# part5.net
KiCad netlist of a schematic drawn in Altium Designer
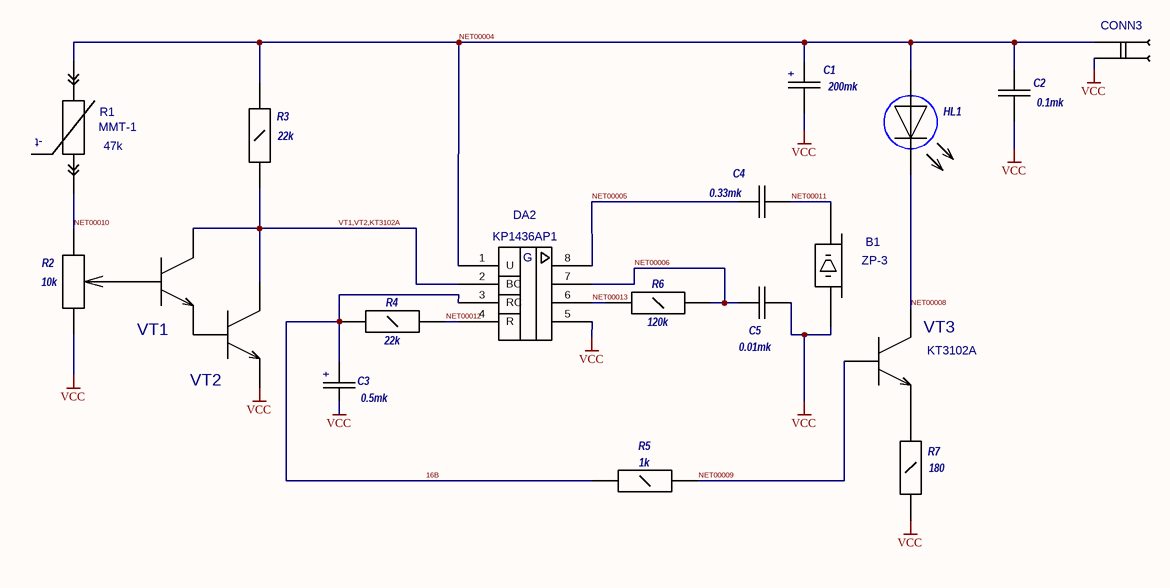
[diagram p0: part5.SCHDOC]

(export (version "E")
  (design (tool "Eeschema 10.0.6"))
  (components
    (comp (ref "B1") (value "ZP-3") (footprint "ЗП-3") (libsource (lib "*") (part "ZP-3")))
    (comp (ref "C1")
      (value "200mk")
      (footprint "К50-29 (17Х6)")
      (description "K50-29 (1;2,2;4,7;10;22 MK)")
      (libsource (lib "*") (part "K50-29 (1;2,2;4,7;10;22 MK)"))
    )
    (comp (ref "C2")
      (value "0.1mk")
      (footprint "K71-6 (10X4)")
      (description "K71-6 (5-30 МК)")
      (libsource (lib "*") (part "K71-6 (5-30 МК)"))
    )
    (comp (ref "C3")
      (value "0.5mk")
      (footprint "К50-29 (17Х6)")
      (description "K50-29 (1;2,2;4,7;10;22 MK)")
      (libsource (lib "*") (part "K50-29 (1;2,2;4,7;10;22 MK)"))
    )
    (comp (ref "C4")
      (value "0.33mk")
      (footprint "K71-6 (10X4)")
      (description "K71-6 (5-30 МК)")
      (libsource (lib "*") (part "K71-6 (5-30 МК)"))
    )
    (comp (ref "C5")
      (value "0.01mk")
      (footprint "K71-6 (10X4)")
      (description "K71-6 (5-30 МК)")
      (libsource (lib "*") (part "K71-6 (5-30 МК)"))
    )
    (comp (ref "CONN3") (value "CONN2X") (footprint "CONN2X") (libsource (lib "*") (part "CONN2X")))
    (comp (ref "DA2") (value "KP1436AP1") (footprint "КР1436АП1") (libsource (lib "*") (part "KP1436AP1")))
    (comp (ref "HL1") (value "АЛ307") (footprint "АЛ307") (libsource (lib "*") (part "АЛ307")))
    (comp (ref "R1")
      (value "MMT-1")
      (footprint "MMT-1")
      (fields (field (name "ALTIUM_VALUE") "47k"))
      (libsource (lib "*") (part "MMT-1"))
    )
    (comp (ref "R2")
      (value "10k")
      (footprint "СП3-38В")
      (description "СП3-38В")
      (libsource (lib "*") (part "СП3-38В"))
    )
    (comp (ref "R3")
      (value "22k")
      (footprint "МЛТ(0.25)")
      (description "МЛТ(0.25)")
      (libsource (lib "*") (part "МЛТ(0.25)"))
    )
    (comp (ref "R4")
      (value "22k")
      (footprint "МЛТ(0.25)")
      (description "МЛТ(0.25)")
      (libsource (lib "*") (part "МЛТ(0.25)"))
    )
    (comp (ref "R5")
      (value "1k")
      (footprint "МЛТ(0.25)")
      (description "МЛТ(0.25)")
      (libsource (lib "*") (part "МЛТ(0.25)"))
    )
    (comp (ref "R6")
      (value "120k")
      (footprint "МЛТ(0.25)")
      (description "МЛТ(0.25)")
      (libsource (lib "*") (part "МЛТ(0.25)"))
    )
    (comp (ref "R7")
      (value "180")
      (footprint "МЛТ(0.25)")
      (description "МЛТ(0.25)")
      (libsource (lib "*") (part "МЛТ(0.25)"))
    )
    (comp (ref "VT1") (value "KT3102A") (footprint "KT3102A") (libsource (lib "*") (part "KT3102A")))
    (comp (ref "VT2") (value "KT3102A") (footprint "KT3102A") (libsource (lib "*") (part "KT3102A")))
    (comp (ref "VT3") (value "KT3102A") (footprint "KT3102A") (libsource (lib "*") (part "KT3102A")))
  )
  (nets
    (net (code "1") (name "/16B") (class "Default")
      (node (ref "C3") (pin "2") (pinfunction "2_2") (pintype "passive"))
      (node (ref "DA2") (pin "3") (pinfunction "RC_3") (pintype "passive"))
      (node (ref "R4") (pin "1") (pinfunction "1_1") (pintype "passive"))
      (node (ref "R5") (pin "1") (pinfunction "1_1") (pintype "passive"))
    )
    (net (code "2") (name "/NET00004") (class "Default")
      (node (ref "C1") (pin "2") (pinfunction "2_2") (pintype "passive"))
      (node (ref "C2") (pin "2") (pinfunction "2_2") (pintype "passive"))
      (node (ref "CONN3") (pin "1") (pintype "passive"))
      (node (ref "DA2") (pin "1") (pinfunction "U_1") (pintype "passive"))
      (node (ref "HL1") (pin "1") (pinfunction "1_1") (pintype "passive"))
      (node (ref "R1") (pin "2") (pinfunction "2_2") (pintype "passive"))
      (node (ref "R3") (pin "1") (pinfunction "1_1") (pintype "passive"))
    )
    (net (code "3") (name "/NET00005") (class "Default")
      (node (ref "C4") (pin "2") (pinfunction "2_2") (pintype "passive"))
      (node (ref "DA2") (pin "8") (pintype "passive"))
    )
    (net (code "4") (name "/NET00006") (class "Default")
      (node (ref "C5") (pin "2") (pinfunction "2_2") (pintype "passive"))
      (node (ref "DA2") (pin "7") (pintype "passive"))
      (node (ref "R6") (pin "2") (pinfunction "2_2") (pintype "passive"))
    )
    (net (code "5") (name "/NET00008") (class "Default")
      (node (ref "HL1") (pin "2") (pinfunction "2_2") (pintype "passive"))
      (node (ref "VT3") (pin "3") (pinfunction "K_3") (pintype "passive"))
    )
    (net (code "6") (name "/NET00009") (class "Default")
      (node (ref "R5") (pin "2") (pinfunction "2_2") (pintype "passive"))
      (node (ref "VT3") (pin "2") (pinfunction "B_2") (pintype "passive"))
    )
    (net (code "7") (name "/NET00010") (class "Default")
      (node (ref "R1") (pin "1") (pinfunction "1_1") (pintype "passive"))
      (node (ref "R2") (pin "1") (pinfunction "1_1") (pintype "passive"))
    )
    (net (code "8") (name "/NET00011") (class "Default")
      (node (ref "B1") (pin "1") (pinfunction "1_1") (pintype "passive"))
      (node (ref "C4") (pin "1") (pinfunction "1_1") (pintype "passive"))
    )
    (net (code "9") (name "/NET00012") (class "Default")
      (node (ref "DA2") (pin "4") (pinfunction "R_4") (pintype "passive"))
      (node (ref "R4") (pin "2") (pinfunction "2_2") (pintype "passive"))
    )
    (net (code "10") (name "/NET00013") (class "Default")
      (node (ref "DA2") (pin "6") (pintype "passive"))
      (node (ref "R6") (pin "1") (pinfunction "1_1") (pintype "passive"))
    )
    (net (code "11") (name "/VT1,VT2,KT3102A") (class "Default")
      (node (ref "DA2") (pin "2") (pinfunction "BC_2") (pintype "passive"))
      (node (ref "R3") (pin "2") (pinfunction "2_2") (pintype "passive"))
      (node (ref "VT1") (pin "3") (pinfunction "K_3") (pintype "passive"))
      (node (ref "VT2") (pin "3") (pinfunction "K_3") (pintype "passive"))
    )
    (net (code "12") (name "Net-(VT1-B)") (class "Default")
      (node (ref "R2") (pin "3") (pinfunction "3_3") (pintype "passive"))
      (node (ref "VT1") (pin "2") (pinfunction "B_2") (pintype "passive"))
    )
    (net (code "13") (name "Net-(VT1-E)") (class "Default")
      (node (ref "VT1") (pin "1") (pinfunction "E_1") (pintype "passive"))
      (node (ref "VT2") (pin "2") (pinfunction "B_2") (pintype "passive"))
    )
    (net (code "14") (name "Net-(VT3-E)") (class "Default")
      (node (ref "R7") (pin "1") (pinfunction "1_1") (pintype "passive"))
      (node (ref "VT3") (pin "1") (pinfunction "E_1") (pintype "passive"))
    )
    (net (code "15") (name "VCC") (class "Default")
      (node (ref "B1") (pin "2") (pinfunction "2_2") (pintype "passive"))
      (node (ref "C1") (pin "1") (pinfunction "1_1") (pintype "passive"))
      (node (ref "C2") (pin "1") (pinfunction "1_1") (pintype "passive"))
      (node (ref "C3") (pin "1") (pinfunction "1_1") (pintype "passive"))
      (node (ref "C5") (pin "1") (pinfunction "1_1") (pintype "passive"))
      (node (ref "CONN3") (pin "2") (pintype "passive"))
      (node (ref "DA2") (pin "5") (pintype "passive"))
      (node (ref "R2") (pin "2") (pinfunction "2_2") (pintype "passive"))
      (node (ref "R7") (pin "2") (pinfunction "2_2") (pintype "passive"))
      (node (ref "VT2") (pin "1") (pinfunction "E_1") (pintype "passive"))
    )
  )
)
